# v4_5.net
KiCad netlist of a schematic drawn in EAGLE
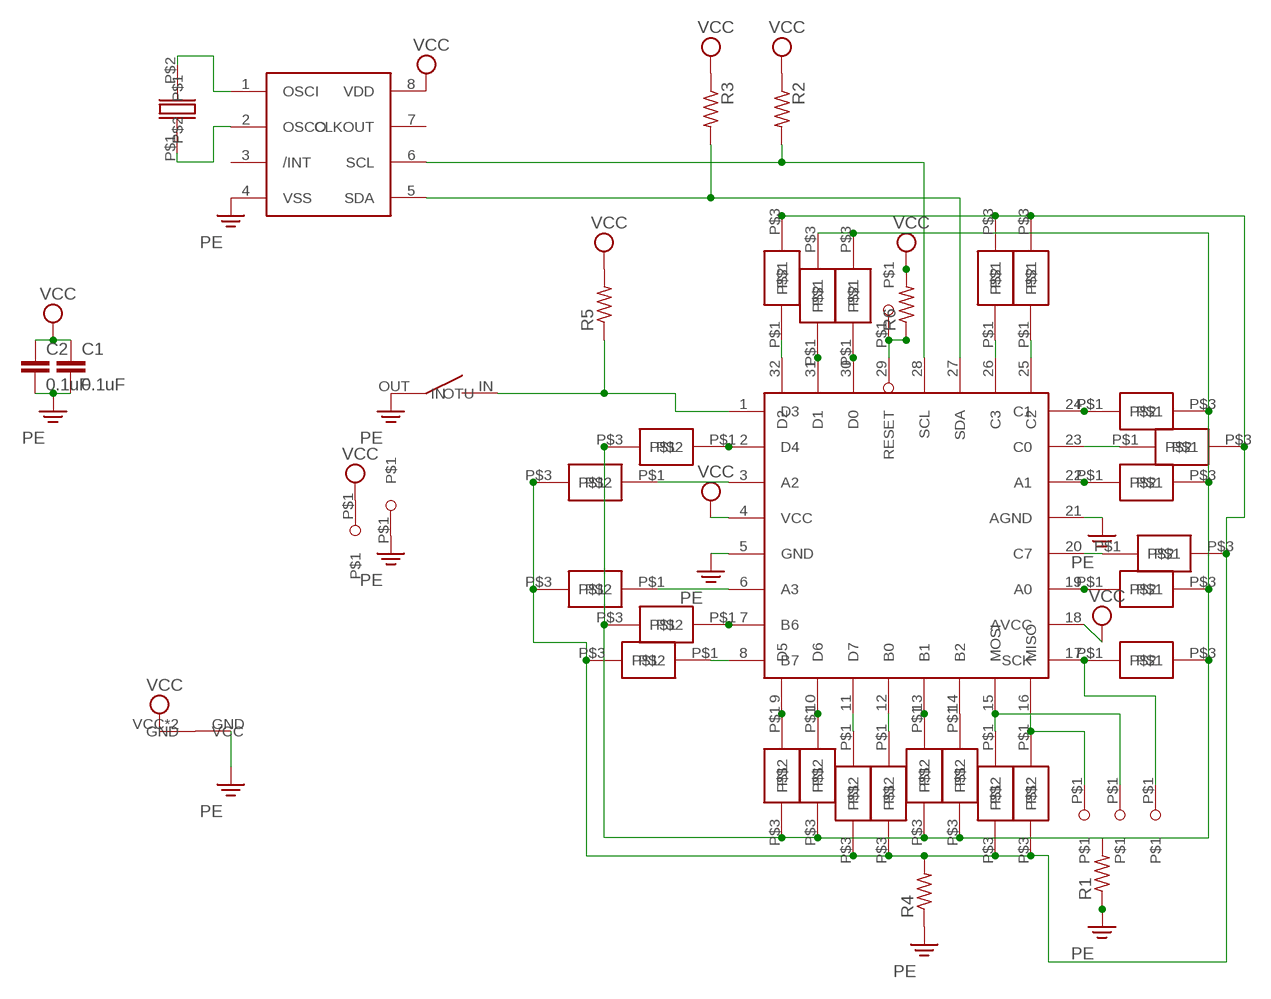
[diagram p0: schematic, sheet 1]

(export (version "E")
  (design (tool "Eeschema 10.0.6"))
  (components
    (comp (ref "C1")
      (value "0.1uF")
      (footprint "eagle-import:C0805K")
      (libsource (lib "eagle-import") (part "C-EUC0805K"))
    )
    (comp (ref "C2")
      (value "0.1uF")
      (footprint "eagle-import:C0805K")
      (libsource (lib "eagle-import") (part "C-EUC0805K"))
    )
    (comp (ref "R1")
      (value "R-US_R0805")
      (footprint "eagle-import:R0805")
      (libsource (lib "eagle-import") (part "R-US_R0805"))
    )
    (comp (ref "R2")
      (value "R-US_R0805")
      (footprint "eagle-import:R0805")
      (libsource (lib "eagle-import") (part "R-US_R0805"))
    )
    (comp (ref "R3")
      (value "R-US_R0805")
      (footprint "eagle-import:R0805")
      (libsource (lib "eagle-import") (part "R-US_R0805"))
    )
    (comp (ref "R4")
      (value "R-US_R0805")
      (footprint "eagle-import:R0805")
      (libsource (lib "eagle-import") (part "R-US_R0805"))
    )
    (comp (ref "R5")
      (value "R-US_R0805")
      (footprint "eagle-import:R0805")
      (libsource (lib "eagle-import") (part "R-US_R0805"))
    )
    (comp (ref "R6")
      (value "R-US_R0805")
      (footprint "eagle-import:R0805")
      (libsource (lib "eagle-import") (part "R-US_R0805"))
    )
    (comp (ref "U$1")
      (value "SMDLED")
      (footprint "eagle-import:SMDLED")
      (libsource (lib "eagle-import") (part "SMDLED"))
    )
    (comp (ref "U$2")
      (value "SMDLED")
      (footprint "eagle-import:SMDLED")
      (libsource (lib "eagle-import") (part "SMDLED"))
    )
    (comp (ref "U$3")
      (value "SMDLED")
      (footprint "eagle-import:SMDLED")
      (libsource (lib "eagle-import") (part "SMDLED"))
    )
    (comp (ref "U$4")
      (value "SMDLED")
      (footprint "eagle-import:SMDLED")
      (libsource (lib "eagle-import") (part "SMDLED"))
    )
    (comp (ref "U$5")
      (value "SMDLED")
      (footprint "eagle-import:SMDLED")
      (libsource (lib "eagle-import") (part "SMDLED"))
    )
    (comp (ref "U$6")
      (value "SMDLED")
      (footprint "eagle-import:SMDLED")
      (libsource (lib "eagle-import") (part "SMDLED"))
    )
    (comp (ref "U$7")
      (value "SMDLED")
      (footprint "eagle-import:SMDLED")
      (libsource (lib "eagle-import") (part "SMDLED"))
    )
    (comp (ref "U$8")
      (value "SMDLED")
      (footprint "eagle-import:SMDLED")
      (libsource (lib "eagle-import") (part "SMDLED"))
    )
    (comp (ref "U$9")
      (value "SMDLED")
      (footprint "eagle-import:SMDLED")
      (libsource (lib "eagle-import") (part "SMDLED"))
    )
    (comp (ref "U$10")
      (value "SMDLED")
      (footprint "eagle-import:SMDLED")
      (libsource (lib "eagle-import") (part "SMDLED"))
    )
    (comp (ref "U$11")
      (value "SMDLED")
      (footprint "eagle-import:SMDLED")
      (libsource (lib "eagle-import") (part "SMDLED"))
    )
    (comp (ref "U$12")
      (value "SMDLED")
      (footprint "eagle-import:SMDLED")
      (libsource (lib "eagle-import") (part "SMDLED"))
    )
    (comp (ref "U$13")
      (value "SMDLED")
      (footprint "eagle-import:SMDLED")
      (libsource (lib "eagle-import") (part "SMDLED"))
    )
    (comp (ref "U$14")
      (value "SMDLED")
      (footprint "eagle-import:SMDLED")
      (libsource (lib "eagle-import") (part "SMDLED"))
    )
    (comp (ref "U$15")
      (value "SMDLED")
      (footprint "eagle-import:SMDLED")
      (libsource (lib "eagle-import") (part "SMDLED"))
    )
    (comp (ref "U$16")
      (value "SMDLED")
      (footprint "eagle-import:SMDLED")
      (libsource (lib "eagle-import") (part "SMDLED"))
    )
    (comp (ref "U$17")
      (value "SMDLED")
      (footprint "eagle-import:SMDLED")
      (libsource (lib "eagle-import") (part "SMDLED"))
    )
    (comp (ref "U$18")
      (value "SMDLED")
      (footprint "eagle-import:SMDLED")
      (libsource (lib "eagle-import") (part "SMDLED"))
    )
    (comp (ref "U$19")
      (value "SMDLED")
      (footprint "eagle-import:SMDLED")
      (libsource (lib "eagle-import") (part "SMDLED"))
    )
    (comp (ref "U$20")
      (value "SMDLED")
      (footprint "eagle-import:SMDLED")
      (libsource (lib "eagle-import") (part "SMDLED"))
    )
    (comp (ref "U$21")
      (value "SMDLED")
      (footprint "eagle-import:SMDLED")
      (libsource (lib "eagle-import") (part "SMDLED"))
    )
    (comp (ref "U$22")
      (value "SMDLED")
      (footprint "eagle-import:SMDLED")
      (libsource (lib "eagle-import") (part "SMDLED"))
    )
    (comp (ref "U$23")
      (value "SMDLED")
      (footprint "eagle-import:SMDLED")
      (libsource (lib "eagle-import") (part "SMDLED"))
    )
    (comp (ref "U$24")
      (value "SMDLED")
      (footprint "eagle-import:SMDLED")
      (libsource (lib "eagle-import") (part "SMDLED"))
    )
    (comp (ref "U$25")
      (value "ATTINY88")
      (footprint "eagle-import:32-TQFT")
      (libsource (lib "eagle-import") (part "ATTINY88"))
    )
    (comp (ref "U$26")
      (value "PAD50")
      (footprint "eagle-import:PAD50")
      (libsource (lib "eagle-import") (part "PAD50"))
    )
    (comp (ref "U$27")
      (value "BAT2009")
      (footprint "eagle-import:BAT2009")
      (libsource (lib "eagle-import") (part "BAT2009"))
    )
    (comp (ref "U$28")
      (value "INT2")
      (footprint "eagle-import:INT2")
      (libsource (lib "eagle-import") (part "INT2"))
    )
    (comp (ref "U$29")
      (value "SMDCRYSTAL")
      (footprint "eagle-import:SMDCRYSTAL")
      (libsource (lib "eagle-import") (part "SMDCRYSTAL"))
    )
    (comp (ref "U$30")
      (value "RTC-SOIC")
      (footprint "eagle-import:8-SOIC")
      (libsource (lib "eagle-import") (part "RTC-SOIC"))
    )
    (comp (ref "U$31")
      (value "PAD50")
      (footprint "eagle-import:PAD50")
      (libsource (lib "eagle-import") (part "PAD50"))
    )
    (comp (ref "U$32")
      (value "PAD50")
      (footprint "eagle-import:PAD50")
      (libsource (lib "eagle-import") (part "PAD50"))
    )
    (comp (ref "U$33")
      (value "PAD50")
      (footprint "eagle-import:PAD50")
      (libsource (lib "eagle-import") (part "PAD50"))
    )
    (comp (ref "U$34")
      (value "PAD50")
      (footprint "eagle-import:PAD50")
      (libsource (lib "eagle-import") (part "PAD50"))
    )
    (comp (ref "U$35")
      (value "PAD50")
      (footprint "eagle-import:PAD50")
      (libsource (lib "eagle-import") (part "PAD50"))
    )
  )
  (nets
    (net (code "1") (name "Net-(U$1-P$2)") (class "Default")
      (node (ref "R4") (pin "2") (pinfunction "2_2") (pintype "passive"))
      (node (ref "U$1") (pin "P$3") (pinfunction "P$2_P$3") (pintype "bidirectional"))
      (node (ref "U$10") (pin "P$3") (pinfunction "P$2_P$3") (pintype "bidirectional"))
      (node (ref "U$14") (pin "P$3") (pinfunction "P$2_P$3") (pintype "bidirectional"))
      (node (ref "U$16") (pin "P$3") (pinfunction "P$2_P$3") (pintype "bidirectional"))
      (node (ref "U$17") (pin "P$3") (pinfunction "P$2_P$3") (pintype "bidirectional"))
      (node (ref "U$20") (pin "P$3") (pinfunction "P$2_P$3") (pintype "bidirectional"))
      (node (ref "U$22") (pin "P$3") (pinfunction "P$2_P$3") (pintype "bidirectional"))
      (node (ref "U$24") (pin "P$3") (pinfunction "P$2_P$3") (pintype "bidirectional"))
      (node (ref "U$4") (pin "P$3") (pinfunction "P$2_P$3") (pintype "bidirectional"))
      (node (ref "U$5") (pin "P$3") (pinfunction "P$2_P$3") (pintype "bidirectional"))
      (node (ref "U$8") (pin "P$3") (pinfunction "P$2_P$3") (pintype "bidirectional"))
      (node (ref "U$9") (pin "P$3") (pinfunction "P$2_P$3") (pintype "bidirectional"))
    )
    (net (code "2") (name "Net-(U$11-P$2)") (class "Default")
      (node (ref "R1") (pin "2") (pinfunction "2_2") (pintype "passive"))
      (node (ref "U$11") (pin "P$3") (pinfunction "P$2_P$3") (pintype "bidirectional"))
      (node (ref "U$12") (pin "P$3") (pinfunction "P$2_P$3") (pintype "bidirectional"))
      (node (ref "U$13") (pin "P$3") (pinfunction "P$2_P$3") (pintype "bidirectional"))
      (node (ref "U$15") (pin "P$3") (pinfunction "P$2_P$3") (pintype "bidirectional"))
      (node (ref "U$18") (pin "P$3") (pinfunction "P$2_P$3") (pintype "bidirectional"))
      (node (ref "U$19") (pin "P$3") (pinfunction "P$2_P$3") (pintype "bidirectional"))
      (node (ref "U$2") (pin "P$3") (pinfunction "P$2_P$3") (pintype "bidirectional"))
      (node (ref "U$21") (pin "P$3") (pinfunction "P$2_P$3") (pintype "bidirectional"))
      (node (ref "U$23") (pin "P$3") (pinfunction "P$2_P$3") (pintype "bidirectional"))
      (node (ref "U$3") (pin "P$3") (pinfunction "P$2_P$3") (pintype "bidirectional"))
      (node (ref "U$6") (pin "P$3") (pinfunction "P$2_P$3") (pintype "bidirectional"))
      (node (ref "U$7") (pin "P$3") (pinfunction "P$2_P$3") (pintype "bidirectional"))
    )
    (net (code "3") (name "Net-(U$25-A0)") (class "Default")
      (node (ref "U$12") (pin "P$1") (pinfunction "P$1_P$1") (pintype "bidirectional"))
      (node (ref "U$25") (pin "19") (pinfunction "A0_19") (pintype "bidirectional"))
    )
    (net (code "4") (name "Net-(U$25-A1)") (class "Default")
      (node (ref "U$21") (pin "P$1") (pinfunction "P$1_P$1") (pintype "bidirectional"))
      (node (ref "U$25") (pin "22") (pinfunction "A1_22") (pintype "bidirectional"))
    )
    (net (code "5") (name "Net-(U$25-A2)") (class "Default")
      (node (ref "U$16") (pin "P$1") (pinfunction "P$1_P$1") (pintype "bidirectional"))
      (node (ref "U$25") (pin "3") (pinfunction "A2_3") (pintype "bidirectional"))
    )
    (net (code "6") (name "Net-(U$25-A3)") (class "Default")
      (node (ref "U$17") (pin "P$1") (pinfunction "P$1_P$1") (pintype "bidirectional"))
      (node (ref "U$25") (pin "6") (pinfunction "A3_6") (pintype "bidirectional"))
    )
    (net (code "7") (name "Net-(U$25-B0)") (class "Default")
      (node (ref "U$1") (pin "P$1") (pinfunction "P$1_P$1") (pintype "bidirectional"))
      (node (ref "U$25") (pin "12") (pinfunction "B0_12") (pintype "bidirectional"))
    )
    (net (code "8") (name "Net-(U$25-B1)") (class "Default")
      (node (ref "U$2") (pin "P$1") (pinfunction "P$1_P$1") (pintype "bidirectional"))
      (node (ref "U$25") (pin "13") (pinfunction "B1_13") (pintype "bidirectional"))
    )
    (net (code "9") (name "Net-(U$25-B2)") (class "Default")
      (node (ref "U$25") (pin "14") (pinfunction "B2_14") (pintype "bidirectional"))
      (node (ref "U$3") (pin "P$1") (pinfunction "P$1_P$1") (pintype "bidirectional"))
    )
    (net (code "10") (name "Net-(U$25-B6)") (class "Default")
      (node (ref "U$25") (pin "7") (pinfunction "B6_7") (pintype "bidirectional"))
      (node (ref "U$7") (pin "P$1") (pinfunction "P$1_P$1") (pintype "bidirectional"))
    )
    (net (code "11") (name "Net-(U$25-B7)") (class "Default")
      (node (ref "U$25") (pin "8") (pinfunction "B7_8") (pintype "bidirectional"))
      (node (ref "U$8") (pin "P$1") (pinfunction "P$1_P$1") (pintype "bidirectional"))
    )
    (net (code "12") (name "Net-(U$25-C0)") (class "Default")
      (node (ref "U$22") (pin "P$1") (pinfunction "P$1_P$1") (pintype "bidirectional"))
      (node (ref "U$25") (pin "23") (pinfunction "C0_23") (pintype "bidirectional"))
    )
    (net (code "13") (name "Net-(U$25-C1)") (class "Default")
      (node (ref "U$25") (pin "24") (pinfunction "C1_24") (pintype "bidirectional"))
      (node (ref "U$6") (pin "P$1") (pinfunction "P$1_P$1") (pintype "bidirectional"))
    )
    (net (code "14") (name "Net-(U$25-C2)") (class "Default")
      (node (ref "U$25") (pin "25") (pinfunction "C2_25") (pintype "bidirectional"))
      (node (ref "U$9") (pin "P$1") (pinfunction "P$1_P$1") (pintype "bidirectional"))
    )
    (net (code "15") (name "Net-(U$25-C3)") (class "Default")
      (node (ref "U$24") (pin "P$1") (pinfunction "P$1_P$1") (pintype "bidirectional"))
      (node (ref "U$25") (pin "26") (pinfunction "C3_26") (pintype "bidirectional"))
    )
    (net (code "16") (name "Net-(U$25-C7)") (class "Default")
      (node (ref "U$10") (pin "P$1") (pinfunction "P$1_P$1") (pintype "bidirectional"))
      (node (ref "U$25") (pin "20") (pinfunction "C7_20") (pintype "bidirectional"))
    )
    (net (code "17") (name "Net-(U$25-D0)") (class "Default")
      (node (ref "U$23") (pin "P$1") (pinfunction "P$1_P$1") (pintype "bidirectional"))
      (node (ref "U$25") (pin "30") (pinfunction "D0_30") (pintype "bidirectional"))
    )
    (net (code "18") (name "Net-(U$25-D1)") (class "Default")
      (node (ref "U$13") (pin "P$1") (pinfunction "P$1_P$1") (pintype "bidirectional"))
      (node (ref "U$25") (pin "31") (pinfunction "D1_31") (pintype "bidirectional"))
    )
    (net (code "19") (name "Net-(U$25-D2)") (class "Default")
      (node (ref "U$14") (pin "P$1") (pinfunction "P$1_P$1") (pintype "bidirectional"))
      (node (ref "U$25") (pin "32") (pinfunction "D2_32") (pintype "bidirectional"))
    )
    (net (code "20") (name "Net-(U$25-D3)") (class "Default")
      (node (ref "R5") (pin "1") (pinfunction "1_1") (pintype "passive"))
      (node (ref "U$25") (pin "1") (pinfunction "D3_1") (pintype "bidirectional"))
      (node (ref "U$28") (pin "IN") (pinfunction "IN_IN") (pintype "bidirectional"))
    )
    (net (code "21") (name "Net-(U$25-D4)") (class "Default")
      (node (ref "U$15") (pin "P$1") (pinfunction "P$1_P$1") (pintype "bidirectional"))
      (node (ref "U$25") (pin "2") (pinfunction "D4_2") (pintype "bidirectional"))
    )
    (net (code "22") (name "Net-(U$25-D5)") (class "Default")
      (node (ref "U$18") (pin "P$1") (pinfunction "P$1_P$1") (pintype "bidirectional"))
      (node (ref "U$25") (pin "9") (pinfunction "D5_9") (pintype "bidirectional"))
    )
    (net (code "23") (name "Net-(U$25-D6)") (class "Default")
      (node (ref "U$19") (pin "P$1") (pinfunction "P$1_P$1") (pintype "bidirectional"))
      (node (ref "U$25") (pin "10") (pinfunction "D6_10") (pintype "bidirectional"))
    )
    (net (code "24") (name "Net-(U$25-D7)") (class "Default")
      (node (ref "U$20") (pin "P$1") (pinfunction "P$1_P$1") (pintype "bidirectional"))
      (node (ref "U$25") (pin "11") (pinfunction "D7_11") (pintype "bidirectional"))
    )
    (net (code "25") (name "Net-(U$25-MISO)") (class "Default")
      (node (ref "U$25") (pin "16") (pinfunction "MISO_16") (pintype "bidirectional"))
      (node (ref "U$32") (pin "P$1") (pinfunction "P$1_P$1") (pintype "bidirectional"))
      (node (ref "U$5") (pin "P$1") (pinfunction "P$1_P$1") (pintype "bidirectional"))
    )
    (net (code "26") (name "Net-(U$25-MOSI)") (class "Default")
      (node (ref "U$25") (pin "15") (pinfunction "MOSI_15") (pintype "bidirectional"))
      (node (ref "U$31") (pin "P$1") (pinfunction "P$1_P$1") (pintype "bidirectional"))
      (node (ref "U$4") (pin "P$1") (pinfunction "P$1_P$1") (pintype "bidirectional"))
    )
    (net (code "27") (name "Net-(U$25-RESET)") (class "Default")
      (node (ref "R6") (pin "1") (pinfunction "1_1") (pintype "passive"))
      (node (ref "U$25") (pin "29") (pinfunction "RESET_29") (pintype "input"))
      (node (ref "U$26") (pin "P$1") (pinfunction "P$1_P$1") (pintype "bidirectional"))
    )
    (net (code "28") (name "Net-(U$25-SCK)") (class "Default")
      (node (ref "U$11") (pin "P$1") (pinfunction "P$1_P$1") (pintype "bidirectional"))
      (node (ref "U$25") (pin "17") (pinfunction "SCK_17") (pintype "bidirectional"))
      (node (ref "U$33") (pin "P$1") (pinfunction "P$1_P$1") (pintype "bidirectional"))
    )
    (net (code "29") (name "Net-(U$25-SCL)") (class "Default")
      (node (ref "R2") (pin "2") (pinfunction "2_2") (pintype "passive"))
      (node (ref "U$25") (pin "28") (pinfunction "SCL_28") (pintype "bidirectional"))
      (node (ref "U$30") (pin "6") (pinfunction "SCL_6") (pintype "input"))
    )
    (net (code "30") (name "Net-(U$25-SDA)") (class "Default")
      (node (ref "R3") (pin "2") (pinfunction "2_2") (pintype "passive"))
      (node (ref "U$25") (pin "27") (pinfunction "SDA_27") (pintype "bidirectional"))
      (node (ref "U$30") (pin "5") (pinfunction "SDA_5") (pintype "bidirectional"))
    )
    (net (code "31") (name "Net-(U$30-OSCI)") (class "Default")
      (node (ref "U$29") (pin "P$2") (pinfunction "P$2_P$2") (pintype "bidirectional"))
      (node (ref "U$30") (pin "1") (pinfunction "OSCI_1") (pintype "input"))
    )
    (net (code "32") (name "Net-(U$30-OSCO)") (class "Default")
      (node (ref "U$29") (pin "P$1") (pinfunction "P$1_P$1") (pintype "bidirectional"))
      (node (ref "U$30") (pin "2") (pinfunction "OSCO_2") (pintype "output"))
    )
    (net (code "33") (name "PE") (class "Default")
      (node (ref "C1") (pin "2") (pinfunction "2_2") (pintype "passive"))
      (node (ref "C2") (pin "2") (pinfunction "2_2") (pintype "passive"))
      (node (ref "R1") (pin "1") (pinfunction "1_1") (pintype "passive"))
      (node (ref "R4") (pin "1") (pinfunction "1_1") (pintype "passive"))
      (node (ref "U$25") (pin "21") (pinfunction "AGND_21") (pintype "power_in"))
      (node (ref "U$25") (pin "5") (pinfunction "GND_5") (pintype "power_in"))
      (node (ref "U$27") (pin "GND") (pinfunction "GND_GND") (pintype "bidirectional"))
      (node (ref "U$28") (pin "OUT") (pinfunction "OTU_OUT") (pintype "bidirectional"))
      (node (ref "U$30") (pin "4") (pinfunction "VSS_4") (pintype "power_in"))
      (node (ref "U$34") (pin "P$1") (pinfunction "P$1_P$1") (pintype "bidirectional"))
    )
    (net (code "34") (name "VCC") (class "Default")
      (node (ref "C1") (pin "1") (pinfunction "1_1") (pintype "passive"))
      (node (ref "C2") (pin "1") (pinfunction "1_1") (pintype "passive"))
      (node (ref "R2") (pin "1") (pinfunction "1_1") (pintype "passive"))
      (node (ref "R3") (pin "1") (pinfunction "1_1") (pintype "passive"))
      (node (ref "R5") (pin "2") (pinfunction "2_2") (pintype "passive"))
      (node (ref "R6") (pin "2") (pinfunction "2_2") (pintype "passive"))
      (node (ref "U$25") (pin "18") (pinfunction "AVCC_18") (pintype "power_in"))
      (node (ref "U$25") (pin "4") (pinfunction "VCC_4") (pintype "power_in"))
      (node (ref "U$27") (pin "VCC") (pinfunction "VCC_VCC") (pintype "bidirectional"))
      (node (ref "U$27") (pin "VCC2") (pinfunction "VCC_VCC2") (pintype "bidirectional"))
      (node (ref "U$30") (pin "8") (pinfunction "VDD_8") (pintype "power_in"))
      (node (ref "U$35") (pin "P$1") (pinfunction "P$1_P$1") (pintype "bidirectional"))
    )
    (net (code "35") (name "unconnected-(U$30-CLKOUT-Pad7)") (class "Default")
      (node (ref "U$30") (pin "7") (pinfunction "CLKOUT_7") (pintype "output"))
    )
    (net (code "36") (name "unconnected-(U$30-{slash}INT-Pad3)") (class "Default")
      (node (ref "U$30") (pin "3") (pinfunction "/INT_3") (pintype "output"))
    )
  )
)
